# mcu_stm32f427.net
KiCad netlist of a schematic drawn in Altium Designer
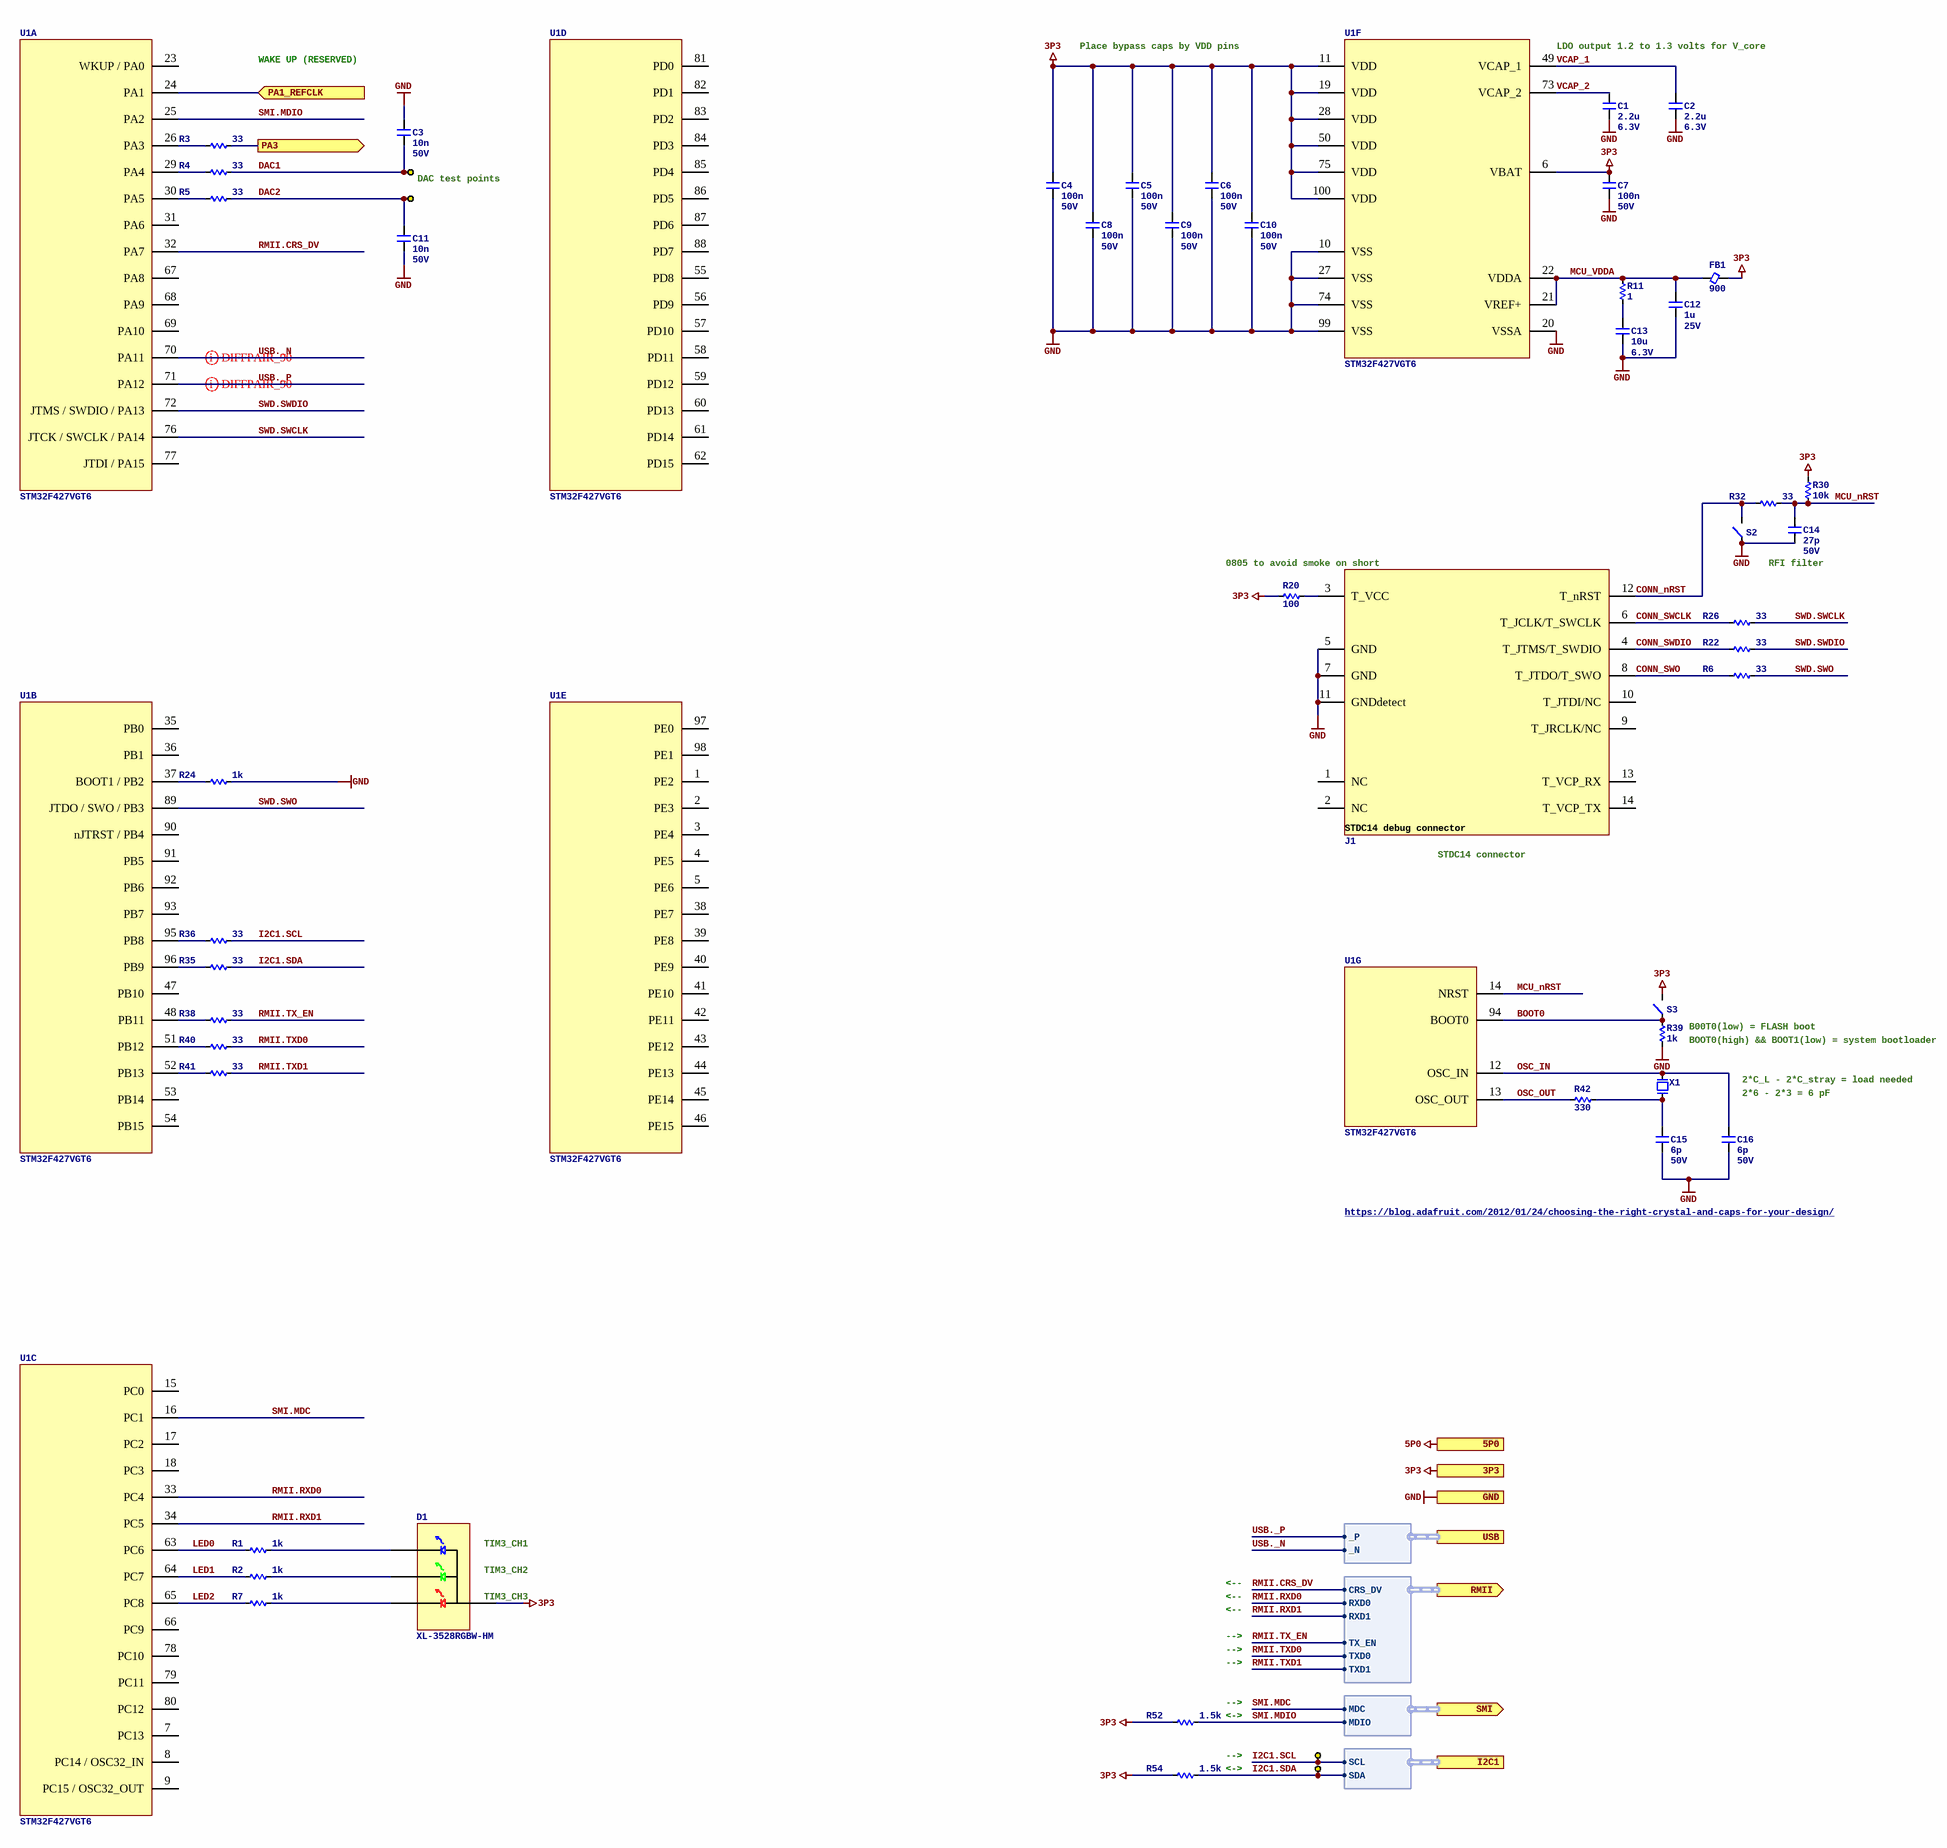
[diagram p0: mcu_stm32f427.SchDoc]

(export (version "E")
  (design (tool "Eeschema 10.0.6"))
  (components
    (comp (ref "C1")
      (value "GCM188R70J225KE22D")
      (footprint "C0603")
      (fields
        (field (name "CAPACITANCE") "2.2u")
        (field (name "MANUFACTURER") "Murata Electronics")
        (field (name "VOLTAGE RATING") "6.3V")
      )
      (libsource (lib "database") (part "__template_cap"))
    )
    (comp (ref "C2")
      (value "GCM188R70J225KE22D")
      (footprint "C0603")
      (fields
        (field (name "CAPACITANCE") "2.2u")
        (field (name "MANUFACTURER") "Murata Electronics")
        (field (name "VOLTAGE RATING") "6.3V")
      )
      (libsource (lib "database") (part "__template_cap"))
    )
    (comp (ref "C3")
      (value "CL05B103KB5NNNC")
      (footprint "C0402")
      (fields
        (field (name "CAPACITANCE") "10n")
        (field (name "MANUFACTURER") "Samsung Electro-Mechanics")
        (field (name "VOLTAGE RATING") "50V")
      )
      (libsource (lib "database") (part "__template_cap"))
    )
    (comp (ref "C4")
      (value "CL05B104KB54PNC")
      (footprint "C0402")
      (fields
        (field (name "CAPACITANCE") "100n")
        (field (name "MANUFACTURER") "Samsung Electro-Mechanics")
        (field (name "VOLTAGE RATING") "50V")
      )
      (libsource (lib "database") (part "__template_cap"))
    )
    (comp (ref "C5")
      (value "CL05B104KB54PNC")
      (footprint "C0402")
      (fields
        (field (name "CAPACITANCE") "100n")
        (field (name "MANUFACTURER") "Samsung Electro-Mechanics")
        (field (name "VOLTAGE RATING") "50V")
      )
      (libsource (lib "database") (part "__template_cap"))
    )
    (comp (ref "C6")
      (value "CL05B104KB54PNC")
      (footprint "C0402")
      (fields
        (field (name "CAPACITANCE") "100n")
        (field (name "MANUFACTURER") "Samsung Electro-Mechanics")
        (field (name "VOLTAGE RATING") "50V")
      )
      (libsource (lib "database") (part "__template_cap"))
    )
    (comp (ref "C7")
      (value "CL05B104KB54PNC")
      (footprint "C0402")
      (fields
        (field (name "CAPACITANCE") "100n")
        (field (name "MANUFACTURER") "Samsung Electro-Mechanics")
        (field (name "VOLTAGE RATING") "50V")
      )
      (libsource (lib "database") (part "__template_cap"))
    )
    (comp (ref "C8")
      (value "CL05B104KB54PNC")
      (footprint "C0402")
      (fields
        (field (name "CAPACITANCE") "100n")
        (field (name "MANUFACTURER") "Samsung Electro-Mechanics")
        (field (name "VOLTAGE RATING") "50V")
      )
      (libsource (lib "database") (part "__template_cap"))
    )
    (comp (ref "C9")
      (value "CL05B104KB54PNC")
      (footprint "C0402")
      (fields
        (field (name "CAPACITANCE") "100n")
        (field (name "MANUFACTURER") "Samsung Electro-Mechanics")
        (field (name "VOLTAGE RATING") "50V")
      )
      (libsource (lib "database") (part "__template_cap"))
    )
    (comp (ref "C10")
      (value "CL05B104KB54PNC")
      (footprint "C0402")
      (fields
        (field (name "CAPACITANCE") "100n")
        (field (name "MANUFACTURER") "Samsung Electro-Mechanics")
        (field (name "VOLTAGE RATING") "50V")
      )
      (libsource (lib "database") (part "__template_cap"))
    )
    (comp (ref "C11")
      (value "CL05B103KB5NNNC")
      (footprint "C0402")
      (fields
        (field (name "CAPACITANCE") "10n")
        (field (name "MANUFACTURER") "Samsung Electro-Mechanics")
        (field (name "VOLTAGE RATING") "50V")
      )
      (libsource (lib "database") (part "__template_cap"))
    )
    (comp (ref "C12")
      (value "CL10B105KA8NNNC")
      (footprint "C0603")
      (fields
        (field (name "CAPACITANCE") "1u")
        (field (name "MANUFACTURER") "Samsung Electro-Mechanics")
        (field (name "VOLTAGE RATING") "25V")
      )
      (libsource (lib "database") (part "__template_cap"))
    )
    (comp (ref "C13")
      (value "CC0805KKX7R5BB106")
      (footprint "C0805")
      (fields
        (field (name "CAPACITANCE") "10u")
        (field (name "MANUFACTURER") "YAGEO")
        (field (name "VOLTAGE RATING") "6.3V")
      )
      (libsource (lib "database") (part "__template_cap"))
    )
    (comp (ref "C14")
      (value "CC0402JRNPO9BN270")
      (footprint "C0402")
      (fields
        (field (name "CAPACITANCE") "27p")
        (field (name "MANUFACTURER") "YAGEO")
        (field (name "VOLTAGE RATING") "50V")
      )
      (libsource (lib "database") (part "__template_cap"))
    )
    (comp (ref "C15")
      (value "CC0402CRNPO9BN6R0")
      (footprint "C0402")
      (fields
        (field (name "CAPACITANCE") "6p")
        (field (name "MANUFACTURER") "YAGEO")
        (field (name "VOLTAGE RATING") "50V")
      )
      (libsource (lib "database") (part "__template_cap"))
    )
    (comp (ref "C16")
      (value "CC0402CRNPO9BN6R0")
      (footprint "C0402")
      (fields
        (field (name "CAPACITANCE") "6p")
        (field (name "MANUFACTURER") "YAGEO")
        (field (name "VOLTAGE RATING") "50V")
      )
      (libsource (lib "database") (part "__template_cap"))
    )
    (comp (ref "D1")
      (value "XL-3528RGBW-HM")
      (footprint "LED_RGB_SMD3528-4P")
      (description "LED Multi-Color Chip Red/Green/Blue 621nm/525nm/468nm 25mA/15mA/15mA 4-Pin PLCC T/R")
      (fields (field (name "MANUFACTURER") "XINGLIGHT"))
      (libsource (lib "SSCP") (part "LED_RGB_XL-3528RGBW-HM"))
    )
    (comp (ref "FB1")
      (value "BLM15PX601SN1D")
      (footprint "FB0402")
      (fields (field (name "MANUFACTURER") "Murata Electronics") (field (name "CURRENT RATING (MA)") "900"))
      (libsource (lib "database") (part "__template_fb"))
    )
    (comp (ref "J1")
      (value "FTSH-107-01-L-DV-K-A")
      (footprint "SAMTEC_FTSH-107-01-L-DV-K-A")
      (description "Connector Header Surface Mount 14 position 0.050\" (1.27mm)")
      (fields (field (name "MANUFACTURER") "Samtec"))
      (libsource (lib "SSCP") (part "CONN_14POS_50MIL_ST_CORTEX_DEBUG_VCP"))
    )
    (comp (ref "R1")
      (value "1k")
      (footprint "R0402")
      (fields
        (field (name "TOLERANCE") "1%")
        (field (name "MANUFACTURER PART NUMBER") "0402WGF1001TCE")
        (field (name "MANUFACTURER") "UNI-ROYAL(Uniroyal Elec)")
      )
      (libsource (lib "database") (part "__template_resistor"))
    )
    (comp (ref "R2")
      (value "1k")
      (footprint "R0402")
      (fields
        (field (name "TOLERANCE") "1%")
        (field (name "MANUFACTURER PART NUMBER") "0402WGF1001TCE")
        (field (name "MANUFACTURER") "UNI-ROYAL(Uniroyal Elec)")
      )
      (libsource (lib "database") (part "__template_resistor"))
    )
    (comp (ref "R3")
      (value "33")
      (footprint "R0402")
      (fields
        (field (name "TOLERANCE") "1%")
        (field (name "MANUFACTURER PART NUMBER") "CRCW040233R0FKED")
        (field (name "MANUFACTURER") "Vishay Intertech")
      )
      (libsource (lib "database") (part "__template_resistor"))
    )
    (comp (ref "R4")
      (value "33")
      (footprint "R0402")
      (fields
        (field (name "TOLERANCE") "1%")
        (field (name "MANUFACTURER PART NUMBER") "CRCW040233R0FKED")
        (field (name "MANUFACTURER") "Vishay Intertech")
      )
      (libsource (lib "database") (part "__template_resistor"))
    )
    (comp (ref "R5")
      (value "33")
      (footprint "R0402")
      (fields
        (field (name "TOLERANCE") "1%")
        (field (name "MANUFACTURER PART NUMBER") "CRCW040233R0FKED")
        (field (name "MANUFACTURER") "Vishay Intertech")
      )
      (libsource (lib "database") (part "__template_resistor"))
    )
    (comp (ref "R6")
      (value "33")
      (footprint "R0402")
      (fields
        (field (name "TOLERANCE") "1%")
        (field (name "MANUFACTURER PART NUMBER") "CRCW040233R0FKED")
        (field (name "MANUFACTURER") "Vishay Intertech")
      )
      (libsource (lib "database") (part "__template_resistor"))
    )
    (comp (ref "R7")
      (value "1k")
      (footprint "R0402")
      (fields
        (field (name "TOLERANCE") "1%")
        (field (name "MANUFACTURER PART NUMBER") "0402WGF1001TCE")
        (field (name "MANUFACTURER") "UNI-ROYAL(Uniroyal Elec)")
      )
      (libsource (lib "database") (part "__template_resistor"))
    )
    (comp (ref "R11")
      (value "1")
      (footprint "R0402")
      (fields
        (field (name "TOLERANCE") "1%")
        (field (name "MANUFACTURER PART NUMBER") "CRCW04021R00FKEDC")
        (field (name "MANUFACTURER") "Vishay Intertech")
      )
      (libsource (lib "database") (part "__template_resistor"))
    )
    (comp (ref "R20")
      (value "100")
      (footprint "R0805")
      (fields
        (field (name "TOLERANCE") "1%")
        (field (name "MANUFACTURER PART NUMBER") "AR05FTC1000")
        (field (name "MANUFACTURER") "Viking Tech")
      )
      (libsource (lib "database") (part "__template_resistor"))
    )
    (comp (ref "R22")
      (value "33")
      (footprint "R0402")
      (fields
        (field (name "TOLERANCE") "1%")
        (field (name "MANUFACTURER PART NUMBER") "CRCW040233R0FKED")
        (field (name "MANUFACTURER") "Vishay Intertech")
      )
      (libsource (lib "database") (part "__template_resistor"))
    )
    (comp (ref "R24")
      (value "1k")
      (footprint "R0402")
      (fields
        (field (name "TOLERANCE") "1%")
        (field (name "MANUFACTURER PART NUMBER") "0402WGF1001TCE")
        (field (name "MANUFACTURER") "UNI-ROYAL(Uniroyal Elec)")
      )
      (libsource (lib "database") (part "__template_resistor"))
    )
    (comp (ref "R26")
      (value "33")
      (footprint "R0402")
      (fields
        (field (name "TOLERANCE") "1%")
        (field (name "MANUFACTURER PART NUMBER") "CRCW040233R0FKED")
        (field (name "MANUFACTURER") "Vishay Intertech")
      )
      (libsource (lib "database") (part "__template_resistor"))
    )
    (comp (ref "R30")
      (value "10k")
      (footprint "R0402")
      (fields
        (field (name "TOLERANCE") "1%")
        (field (name "MANUFACTURER PART NUMBER") "0402WGF1002TCE")
        (field (name "MANUFACTURER") "UNI-ROYAL(Uniroyal Elec)")
      )
      (libsource (lib "database") (part "__template_resistor"))
    )
    (comp (ref "R32")
      (value "33")
      (footprint "R0402")
      (fields
        (field (name "TOLERANCE") "1%")
        (field (name "MANUFACTURER PART NUMBER") "CRCW040233R0FKED")
        (field (name "MANUFACTURER") "Vishay Intertech")
      )
      (libsource (lib "database") (part "__template_resistor"))
    )
    (comp (ref "R35")
      (value "33")
      (footprint "R0402")
      (fields
        (field (name "TOLERANCE") "1%")
        (field (name "MANUFACTURER PART NUMBER") "CRCW040233R0FKED")
        (field (name "MANUFACTURER") "Vishay Intertech")
      )
      (libsource (lib "database") (part "__template_resistor"))
    )
    (comp (ref "R36")
      (value "33")
      (footprint "R0402")
      (fields
        (field (name "TOLERANCE") "1%")
        (field (name "MANUFACTURER PART NUMBER") "CRCW040233R0FKED")
        (field (name "MANUFACTURER") "Vishay Intertech")
      )
      (libsource (lib "database") (part "__template_resistor"))
    )
    (comp (ref "R38")
      (value "33")
      (footprint "R0402")
      (fields
        (field (name "TOLERANCE") "1%")
        (field (name "MANUFACTURER PART NUMBER") "CRCW040233R0FKED")
        (field (name "MANUFACTURER") "Vishay Intertech")
      )
      (libsource (lib "database") (part "__template_resistor"))
    )
    (comp (ref "R39")
      (value "1k")
      (footprint "R0402")
      (fields
        (field (name "TOLERANCE") "1%")
        (field (name "MANUFACTURER PART NUMBER") "0402WGF1001TCE")
        (field (name "MANUFACTURER") "UNI-ROYAL(Uniroyal Elec)")
      )
      (libsource (lib "database") (part "__template_resistor"))
    )
    (comp (ref "R40")
      (value "33")
      (footprint "R0402")
      (fields
        (field (name "TOLERANCE") "1%")
        (field (name "MANUFACTURER PART NUMBER") "CRCW040233R0FKED")
        (field (name "MANUFACTURER") "Vishay Intertech")
      )
      (libsource (lib "database") (part "__template_resistor"))
    )
    (comp (ref "R41")
      (value "33")
      (footprint "R0402")
      (fields
        (field (name "TOLERANCE") "1%")
        (field (name "MANUFACTURER PART NUMBER") "CRCW040233R0FKED")
        (field (name "MANUFACTURER") "Vishay Intertech")
      )
      (libsource (lib "database") (part "__template_resistor"))
    )
    (comp (ref "R42")
      (value "330")
      (footprint "R0402")
      (fields
        (field (name "TOLERANCE") "1%")
        (field (name "MANUFACTURER PART NUMBER") "0402WGF3300TCE")
        (field (name "MANUFACTURER") "UNI-ROYAL(Uniroyal Elec)")
      )
      (libsource (lib "database") (part "__template_resistor"))
    )
    (comp (ref "R52")
      (value "1.5k")
      (footprint "R0402")
      (fields
        (field (name "TOLERANCE") "1%")
        (field (name "MANUFACTURER PART NUMBER") "0402WGF1501TCE")
        (field (name "MANUFACTURER") "UNI-ROYAL(Uniroyal Elec)")
      )
      (libsource (lib "database") (part "__template_resistor"))
    )
    (comp (ref "R54")
      (value "1.5k")
      (footprint "R0402")
      (fields
        (field (name "TOLERANCE") "1%")
        (field (name "MANUFACTURER PART NUMBER") "0402WGF1501TCE")
        (field (name "MANUFACTURER") "UNI-ROYAL(Uniroyal Elec)")
      )
      (libsource (lib "database") (part "__template_resistor"))
    )
    (comp (ref "S2")
      (value "TS-1092S-B3D2-G")
      (footprint "SWITCH_TS-1092S-B3D2-G")
      (description "SWITCH TACTILE SPST-NO")
      (fields (field (name "MANUFACTURER") "Yuandi"))
      (libsource (lib "SSCP") (part "SWITCH_TS-1092S-B3D2-G"))
    )
    (comp (ref "S3")
      (value "TS-1092S-B3D2-G")
      (footprint "SWITCH_TS-1092S-B3D2-G")
      (description "SWITCH TACTILE SPST-NO")
      (fields (field (name "MANUFACTURER") "Yuandi"))
      (libsource (lib "SSCP") (part "SWITCH_TS-1092S-B3D2-G"))
    )
    (comp (ref "TP1")
      (value "~")
      (footprint "TP_RH-5002")
      (description "THT white clip turret")
      (fields (field (name "MANUFACTURER PART NUMBER") "RH-5002") (field (name "MANUFACTURER") "ronghe"))
      (libsource (lib "database") (part "__template_testpoint"))
    )
    (comp (ref "TP2")
      (value "~")
      (footprint "TP_RH-5002")
      (description "THT white clip turret")
      (fields (field (name "MANUFACTURER PART NUMBER") "RH-5002") (field (name "MANUFACTURER") "ronghe"))
      (libsource (lib "database") (part "__template_testpoint"))
    )
    (comp (ref "TP62")
      (value "~")
      (footprint "TP_GRABBY")
      (description "EMBEDDED TEST POINT FOR SALEAE TEST CLIPS")
      (libsource (lib "SSCP") (part "TEST_GRABBER"))
    )
    (comp (ref "TP63")
      (value "~")
      (footprint "TP_GRABBY")
      (description "EMBEDDED TEST POINT FOR SALEAE TEST CLIPS")
      (libsource (lib "SSCP") (part "TEST_GRABBER"))
    )
    (comp (ref "U1")
      (value "STM32F427VGT6")
      (footprint "100TQFP14")
      (description "ARM Cortex®-M4 STM32F4 Microcontroller IC 32-Bit 180MHz 1MB (1M x 8) FLASH 100-LQFP (14x14)")
      (fields
        (field (name "MANUFACTURER PART NUMBER") "STM32F427VGT6")
        (field (name "MANUFACTURER") "ST Microelectronics")
      )
      (libsource (lib "SSCP") (part "MCU_STM32F427VGT6"))
    )
    (comp (ref "X1")
      (value "XTAL_XRCGB25M000F3A00R0")
      (footprint "4_SMD_2.0X1.6MM")
      (description "CRYSTAL 25.000MHZ 6PF SMD")
      (fields
        (field (name "MANUFACTURER") "Murata")
        (field (name "MANUFACTURER PART NUMBER") "XRCGB25M000F3A00R0")
      )
      (libsource (lib "SSCP") (part "XTAL_XRCGB25M000F3A00R0"))
    )
  )
  (nets
    (net (code "5") (name "/BOOT0") (class "Default")
      (node (ref "R39") (pin "1") (pintype "passive"))
      (node (ref "S3") (pin "1") (pintype "passive"))
      (node (ref "U1") (pin "94") (pinfunction "BOOT0_94") (pintype "passive"))
    )
    (net (code "6") (name "/CONN_SWCLK") (class "Default")
      (node (ref "J1") (pin "6") (pinfunction "T_JCLK/T_SWCLK_6") (pintype "passive"))
      (node (ref "R26") (pin "2") (pintype "passive"))
    )
    (net (code "7") (name "/CONN_SWDIO") (class "Default")
      (node (ref "J1") (pin "4") (pinfunction "T_JTMS/T_SWDIO_4") (pintype "passive"))
      (node (ref "R22") (pin "2") (pintype "passive"))
    )
    (net (code "8") (name "/CONN_SWO") (class "Default")
      (node (ref "J1") (pin "8") (pinfunction "T_JTDO/T_SWO_8") (pintype "passive"))
      (node (ref "R6") (pin "2") (pintype "passive"))
    )
    (net (code "9") (name "/CONN_nRST") (class "Default")
      (node (ref "J1") (pin "12") (pinfunction "T_nRST_12") (pintype "passive"))
      (node (ref "R32") (pin "2") (pintype "passive"))
      (node (ref "S2") (pin "2") (pintype "passive"))
    )
    (net (code "10") (name "/DAC1") (class "Default")
      (node (ref "C3") (pin "1") (pintype "passive"))
      (node (ref "R4") (pin "1") (pintype "passive"))
      (node (ref "TP1") (pin "1") (pintype "passive"))
    )
    (net (code "11") (name "/DAC2") (class "Default")
      (node (ref "C11") (pin "1") (pintype "passive"))
      (node (ref "R5") (pin "1") (pintype "passive"))
      (node (ref "TP2") (pin "1") (pintype "passive"))
    )
    (net (code "12") (name "/I2C1.SCL") (class "Default")
      (node (ref "R36") (pin "1") (pintype "passive"))
      (node (ref "TP62") (pin "1") (pintype "passive"))
    )
    (net (code "13") (name "/I2C1.SDA") (class "Default")
      (node (ref "R35") (pin "1") (pintype "passive"))
      (node (ref "R54") (pin "1") (pintype "passive"))
      (node (ref "TP63") (pin "1") (pintype "passive"))
    )
    (net (code "14") (name "/LED0") (class "Default")
      (node (ref "R1") (pin "2") (pintype "passive"))
      (node (ref "U1") (pin "63") (pinfunction "PC6_63") (pintype "passive"))
    )
    (net (code "15") (name "/LED1") (class "Default")
      (node (ref "R2") (pin "2") (pintype "passive"))
      (node (ref "U1") (pin "64") (pinfunction "PC7_64") (pintype "passive"))
    )
    (net (code "16") (name "/LED2") (class "Default")
      (node (ref "R7") (pin "2") (pintype "passive"))
      (node (ref "U1") (pin "65") (pinfunction "PC8_65") (pintype "passive"))
    )
    (net (code "17") (name "/MCU_VDDA") (class "Default")
      (node (ref "C12") (pin "1") (pintype "passive"))
      (node (ref "FB1") (pin "1") (pintype "passive"))
      (node (ref "R11") (pin "2") (pintype "passive"))
      (node (ref "U1") (pin "21") (pinfunction "VREF+_21") (pintype "passive"))
      (node (ref "U1") (pin "22") (pinfunction "VDDA_22") (pintype "passive"))
    )
    (net (code "18") (name "/MCU_nRST") (class "Default")
      (node (ref "C14") (pin "1") (pintype "passive"))
      (node (ref "R30") (pin "2") (pintype "passive"))
      (node (ref "R32") (pin "1") (pintype "passive"))
      (node (ref "U1") (pin "14") (pinfunction "NRST_14") (pintype "passive"))
    )
    (net (code "19") (name "/OSC_IN") (class "Default")
      (node (ref "C16") (pin "1") (pintype "passive"))
      (node (ref "U1") (pin "12") (pinfunction "OSC_IN_12") (pintype "passive"))
      (node (ref "X1") (pin "3") (pinfunction "3_3") (pintype "passive"))
    )
    (net (code "20") (name "/OSC_OUT") (class "Default")
      (node (ref "R42") (pin "1") (pintype "passive"))
      (node (ref "U1") (pin "13") (pinfunction "OSC_OUT_13") (pintype "passive"))
    )
    (net (code "21") (name "/PA1_REFCLK") (class "Default")
      (node (ref "U1") (pin "24") (pinfunction "PA1_24") (pintype "passive"))
    )
    (net (code "22") (name "/PA3") (class "Default") (node (ref "R3") (pin "1") (pintype "passive")))
    (net (code "23") (name "/RMII.CRS_DV") (class "Default")
      (node (ref "U1") (pin "32") (pinfunction "PA7_32") (pintype "passive"))
    )
    (net (code "24") (name "/RMII.RXD0") (class "Default")
      (node (ref "U1") (pin "33") (pinfunction "PC4_33") (pintype "passive"))
    )
    (net (code "25") (name "/RMII.RXD1") (class "Default")
      (node (ref "U1") (pin "34") (pinfunction "PC5_34") (pintype "passive"))
    )
    (net (code "26") (name "/RMII.TXD0") (class "Default") (node (ref "R40") (pin "1") (pintype "passive")))
    (net (code "27") (name "/RMII.TXD1") (class "Default") (node (ref "R41") (pin "1") (pintype "passive")))
    (net (code "28") (name "/RMII.TX_EN") (class "Default") (node (ref "R38") (pin "1") (pintype "passive")))
    (net (code "29") (name "/SMI.MDC") (class "Default")
      (node (ref "U1") (pin "16") (pinfunction "PC1_16") (pintype "passive"))
    )
    (net (code "30") (name "/SMI.MDIO") (class "Default")
      (node (ref "R52") (pin "1") (pintype "passive"))
      (node (ref "U1") (pin "25") (pinfunction "PA2_25") (pintype "passive"))
    )
    (net (code "31") (name "/SWD.SWCLK") (class "Default")
      (node (ref "R26") (pin "1") (pintype "passive"))
      (node (ref "U1") (pin "76") (pinfunction "JTCK_/_SWCLK_/_PA14_76") (pintype "passive"))
    )
    (net (code "32") (name "/SWD.SWDIO") (class "Default")
      (node (ref "R22") (pin "1") (pintype "passive"))
      (node (ref "U1") (pin "72") (pinfunction "JTMS_/_SWDIO_/_PA13_72") (pintype "passive"))
    )
    (net (code "33") (name "/SWD.SWO") (class "Default")
      (node (ref "R6") (pin "1") (pintype "passive"))
      (node (ref "U1") (pin "89") (pinfunction "JTDO_/_SWO_/_PB3_89") (pintype "passive"))
    )
    (net (code "34") (name "/USB._N") (class "Default")
      (node (ref "U1") (pin "70") (pinfunction "PA11_70") (pintype "passive"))
    )
    (net (code "35") (name "/USB._P") (class "Default")
      (node (ref "U1") (pin "71") (pinfunction "PA12_71") (pintype "passive"))
    )
    (net (code "36") (name "/VCAP_1") (class "Default")
      (node (ref "C2") (pin "1") (pintype "passive"))
      (node (ref "U1") (pin "49") (pinfunction "VCAP_1_49") (pintype "passive"))
    )
    (net (code "37") (name "/VCAP_2") (class "Default")
      (node (ref "C1") (pin "1") (pintype "passive"))
      (node (ref "U1") (pin "73") (pinfunction "VCAP_2_73") (pintype "passive"))
    )
    (net (code "42") (name "3P3") (class "Default")
      (node (ref "C10") (pin "1") (pintype "passive"))
      (node (ref "C4") (pin "1") (pintype "passive"))
      (node (ref "C5") (pin "1") (pintype "passive"))
      (node (ref "C6") (pin "1") (pintype "passive"))
      (node (ref "C7") (pin "1") (pintype "passive"))
      (node (ref "C8") (pin "1") (pintype "passive"))
      (node (ref "C9") (pin "1") (pintype "passive"))
      (node (ref "D1") (pin "2") (pintype "passive"))
      (node (ref "FB1") (pin "2") (pintype "passive"))
      (node (ref "R20") (pin "2") (pintype "passive"))
      (node (ref "R30") (pin "1") (pintype "passive"))
      (node (ref "R52") (pin "2") (pintype "passive"))
      (node (ref "R54") (pin "2") (pintype "passive"))
      (node (ref "S3") (pin "2") (pintype "passive"))
      (node (ref "U1") (pin "100") (pinfunction "VDD_100") (pintype "passive"))
      (node (ref "U1") (pin "11") (pinfunction "VDD_11") (pintype "passive"))
      (node (ref "U1") (pin "19") (pinfunction "VDD_19") (pintype "passive"))
      (node (ref "U1") (pin "28") (pinfunction "VDD_28") (pintype "passive"))
      (node (ref "U1") (pin "50") (pinfunction "VDD_50") (pintype "passive"))
      (node (ref "U1") (pin "6") (pinfunction "VBAT_6") (pintype "passive"))
      (node (ref "U1") (pin "75") (pinfunction "VDD_75") (pintype "passive"))
    )
    (net (code "44") (name "GND") (class "Default")
      (node (ref "C1") (pin "2") (pintype "passive"))
      (node (ref "C10") (pin "2") (pintype "passive"))
      (node (ref "C11") (pin "2") (pintype "passive"))
      (node (ref "C12") (pin "2") (pintype "passive"))
      (node (ref "C13") (pin "2") (pintype "passive"))
      (node (ref "C14") (pin "2") (pintype "passive"))
      (node (ref "C15") (pin "2") (pintype "passive"))
      (node (ref "C16") (pin "2") (pintype "passive"))
      (node (ref "C2") (pin "2") (pintype "passive"))
      (node (ref "C3") (pin "2") (pintype "passive"))
      (node (ref "C4") (pin "2") (pintype "passive"))
      (node (ref "C5") (pin "2") (pintype "passive"))
      (node (ref "C6") (pin "2") (pintype "passive"))
      (node (ref "C7") (pin "2") (pintype "passive"))
      (node (ref "C8") (pin "2") (pintype "passive"))
      (node (ref "C9") (pin "2") (pintype "passive"))
      (node (ref "J1") (pin "11") (pinfunction "GNDdetect_11") (pintype "passive"))
      (node (ref "J1") (pin "5") (pinfunction "GND_5") (pintype "passive"))
      (node (ref "J1") (pin "7") (pinfunction "GND_7") (pintype "passive"))
      (node (ref "R24") (pin "1") (pintype "passive"))
      (node (ref "R39") (pin "2") (pintype "passive"))
      (node (ref "S2") (pin "1") (pintype "passive"))
      (node (ref "U1") (pin "10") (pinfunction "VSS_10") (pintype "passive"))
      (node (ref "U1") (pin "20") (pinfunction "VSSA_20") (pintype "passive"))
      (node (ref "U1") (pin "27") (pinfunction "VSS_27") (pintype "passive"))
      (node (ref "U1") (pin "74") (pinfunction "VSS_74") (pintype "passive"))
      (node (ref "U1") (pin "99") (pinfunction "VSS_99") (pintype "passive"))
    )
    (net (code "45") (name "Net-(C13-Pad1)") (class "Default")
      (node (ref "C13") (pin "1") (pintype "passive"))
      (node (ref "R11") (pin "1") (pintype "passive"))
    )
    (net (code "46") (name "Net-(C15-Pad1)") (class "Default")
      (node (ref "C15") (pin "1") (pintype "passive"))
      (node (ref "R42") (pin "2") (pintype "passive"))
      (node (ref "X1") (pin "1") (pinfunction "1_1") (pintype "passive"))
    )
    (net (code "47") (name "Net-(D1-Pad1)") (class "Default")
      (node (ref "D1") (pin "1") (pintype "passive"))
      (node (ref "R7") (pin "1") (pintype "passive"))
    )
    (net (code "48") (name "Net-(D1-Pad3)") (class "Default")
      (node (ref "D1") (pin "3") (pintype "passive"))
      (node (ref "R2") (pin "1") (pintype "passive"))
    )
    (net (code "49") (name "Net-(D1-Pad4)") (class "Default")
      (node (ref "D1") (pin "4") (pintype "passive"))
      (node (ref "R1") (pin "1") (pintype "passive"))
    )
    (net (code "50") (name "Net-(J1-T_VCC)") (class "Default")
      (node (ref "J1") (pin "3") (pinfunction "T_VCC_3") (pintype "passive"))
      (node (ref "R20") (pin "1") (pintype "passive"))
    )
    (net (code "51") (name "Net-(U1A-PA3)") (class "Default")
      (node (ref "R3") (pin "2") (pintype "passive"))
      (node (ref "U1") (pin "26") (pinfunction "PA3_26") (pintype "passive"))
    )
    (net (code "52") (name "Net-(U1A-PA4)") (class "Default")
      (node (ref "R4") (pin "2") (pintype "passive"))
      (node (ref "U1") (pin "29") (pinfunction "PA4_29") (pintype "passive"))
    )
    (net (code "53") (name "Net-(U1A-PA5)") (class "Default")
      (node (ref "R5") (pin "2") (pintype "passive"))
      (node (ref "U1") (pin "30") (pinfunction "PA5_30") (pintype "passive"))
    )
    (net (code "54") (name "Net-(U1B-BOOT1_{slash}_PB2)") (class "Default")
      (node (ref "R24") (pin "2") (pintype "passive"))
      (node (ref "U1") (pin "37") (pinfunction "BOOT1_/_PB2_37") (pintype "passive"))
    )
    (net (code "55") (name "Net-(U1B-PB8)") (class "Default")
      (node (ref "R36") (pin "2") (pintype "passive"))
      (node (ref "U1") (pin "95") (pinfunction "PB8_95") (pintype "passive"))
    )
    (net (code "56") (name "Net-(U1B-PB9)") (class "Default")
      (node (ref "R35") (pin "2") (pintype "passive"))
      (node (ref "U1") (pin "96") (pinfunction "PB9_96") (pintype "passive"))
    )
    (net (code "57") (name "Net-(U1B-PB11)") (class "Default")
      (node (ref "R38") (pin "2") (pintype "passive"))
      (node (ref "U1") (pin "48") (pinfunction "PB11_48") (pintype "passive"))
    )
    (net (code "58") (name "Net-(U1B-PB12)") (class "Default")
      (node (ref "R40") (pin "2") (pintype "passive"))
      (node (ref "U1") (pin "51") (pinfunction "PB12_51") (pintype "passive"))
    )
    (net (code "59") (name "Net-(U1B-PB13)") (class "Default")
      (node (ref "R41") (pin "2") (pintype "passive"))
      (node (ref "U1") (pin "52") (pinfunction "PB13_52") (pintype "passive"))
    )
    (net (code "60") (name "unconnected-(J1-NC-Pad1)") (class "Default")
      (node (ref "J1") (pin "1") (pinfunction "NC_1") (pintype "passive"))
    )
    (net (code "61") (name "unconnected-(J1-NC-Pad2)") (class "Default")
      (node (ref "J1") (pin "2") (pinfunction "NC_2") (pintype "passive"))
    )
    (net (code "62") (name "unconnected-(J1-T_JRCLK{slash}NC-Pad9)") (class "Default")
      (node (ref "J1") (pin "9") (pinfunction "T_JRCLK/NC_9") (pintype "passive"))
    )
    (net (code "63") (name "unconnected-(J1-T_JTDI{slash}NC-Pad10)") (class "Default")
      (node (ref "J1") (pin "10") (pinfunction "T_JTDI/NC_10") (pintype "passive"))
    )
    (net (code "64") (name "unconnected-(J1-T_VCP_RX-Pad13)") (class "Default")
      (node (ref "J1") (pin "13") (pinfunction "T_VCP_RX_13") (pintype "passive"))
    )
    (net (code "65") (name "unconnected-(J1-T_VCP_TX-Pad14)") (class "Default")
      (node (ref "J1") (pin "14") (pinfunction "T_VCP_TX_14") (pintype "passive"))
    )
    (net (code "66") (name "unconnected-(U1A-JTDI_{slash}_PA15-Pad77)") (class "Default")
      (node (ref "U1") (pin "77") (pinfunction "JTDI_/_PA15_77") (pintype "passive"))
    )
    (net (code "67") (name "unconnected-(U1A-PA6-Pad31)") (class "Default")
      (node (ref "U1") (pin "31") (pinfunction "PA6_31") (pintype "passive"))
    )
    (net (code "68") (name "unconnected-(U1A-PA8-Pad67)") (class "Default")
      (node (ref "U1") (pin "67") (pinfunction "PA8_67") (pintype "passive"))
    )
    (net (code "69") (name "unconnected-(U1A-PA9-Pad68)") (class "Default")
      (node (ref "U1") (pin "68") (pinfunction "PA9_68") (pintype "passive"))
    )
    (net (code "70") (name "unconnected-(U1A-PA10-Pad69)") (class "Default")
      (node (ref "U1") (pin "69") (pinfunction "PA10_69") (pintype "passive"))
    )
    (net (code "71") (name "unconnected-(U1A-WKUP_{slash}_PA0-Pad23)") (class "Default")
      (node (ref "U1") (pin "23") (pinfunction "WKUP_/_PA0_23") (pintype "passive"))
    )
    (net (code "72") (name "unconnected-(U1B-PB0-Pad35)") (class "Default")
      (node (ref "U1") (pin "35") (pinfunction "PB0_35") (pintype "passive"))
    )
    (net (code "73") (name "unconnected-(U1B-PB1-Pad36)") (class "Default")
      (node (ref "U1") (pin "36") (pinfunction "PB1_36") (pintype "passive"))
    )
    (net (code "74") (name "unconnected-(U1B-PB5-Pad91)") (class "Default")
      (node (ref "U1") (pin "91") (pinfunction "PB5_91") (pintype "passive"))
    )
    (net (code "75") (name "unconnected-(U1B-PB6-Pad92)") (class "Default")
      (node (ref "U1") (pin "92") (pinfunction "PB6_92") (pintype "passive"))
    )
    (net (code "76") (name "unconnected-(U1B-PB7-Pad93)") (class "Default")
      (node (ref "U1") (pin "93") (pinfunction "PB7_93") (pintype "passive"))
    )
    (net (code "77") (name "unconnected-(U1B-PB10-Pad47)") (class "Default")
      (node (ref "U1") (pin "47") (pinfunction "PB10_47") (pintype "passive"))
    )
    (net (code "78") (name "unconnected-(U1B-PB14-Pad53)") (class "Default")
      (node (ref "U1") (pin "53") (pinfunction "PB14_53") (pintype "passive"))
    )
    (net (code "79") (name "unconnected-(U1B-PB15-Pad54)") (class "Default")
      (node (ref "U1") (pin "54") (pinfunction "PB15_54") (pintype "passive"))
    )
    (net (code "80") (name "unconnected-(U1B-nJTRST_{slash}_PB4-Pad90)") (class "Default")
      (node (ref "U1") (pin "90") (pinfunction "nJTRST_/_PB4_90") (pintype "passive"))
    )
    (net (code "81") (name "unconnected-(U1C-PC0-Pad15)") (class "Default")
      (node (ref "U1") (pin "15") (pinfunction "PC0_15") (pintype "passive"))
    )
    (net (code "82") (name "unconnected-(U1C-PC2-Pad17)") (class "Default")
      (node (ref "U1") (pin "17") (pinfunction "PC2_17") (pintype "passive"))
    )
    (net (code "83") (name "unconnected-(U1C-PC3-Pad18)") (class "Default")
      (node (ref "U1") (pin "18") (pinfunction "PC3_18") (pintype "passive"))
    )
    (net (code "84") (name "unconnected-(U1C-PC9-Pad66)") (class "Default")
      (node (ref "U1") (pin "66") (pinfunction "PC9_66") (pintype "passive"))
    )
    (net (code "85") (name "unconnected-(U1C-PC10-Pad78)") (class "Default")
      (node (ref "U1") (pin "78") (pinfunction "PC10_78") (pintype "passive"))
    )
    (net (code "86") (name "unconnected-(U1C-PC11-Pad79)") (class "Default")
      (node (ref "U1") (pin "79") (pinfunction "PC11_79") (pintype "passive"))
    )
    (net (code "87") (name "unconnected-(U1C-PC12-Pad80)") (class "Default")
      (node (ref "U1") (pin "80") (pinfunction "PC12_80") (pintype "passive"))
    )
    (net (code "88") (name "unconnected-(U1C-PC13-Pad7)") (class "Default")
      (node (ref "U1") (pin "7") (pinfunction "PC13_7") (pintype "passive"))
    )
    (net (code "89") (name "unconnected-(U1C-PC14_{slash}_OSC32_IN-Pad8)") (class "Default")
      (node (ref "U1") (pin "8") (pinfunction "PC14_/_OSC32_IN_8") (pintype "passive"))
    )
    (net (code "90") (name "unconnected-(U1C-PC15_{slash}_OSC32_OUT-Pad9)") (class "Default")
      (node (ref "U1") (pin "9") (pinfunction "PC15_/_OSC32_OUT_9") (pintype "passive"))
    )
    (net (code "91") (name "unconnected-(U1D-PD0-Pad81)") (class "Default")
      (node (ref "U1") (pin "81") (pinfunction "PD0_81") (pintype "passive"))
    )
    (net (code "92") (name "unconnected-(U1D-PD1-Pad82)") (class "Default")
      (node (ref "U1") (pin "82") (pinfunction "PD1_82") (pintype "passive"))
    )
    (net (code "93") (name "unconnected-(U1D-PD2-Pad83)") (class "Default")
      (node (ref "U1") (pin "83") (pinfunction "PD2_83") (pintype "passive"))
    )
    (net (code "94") (name "unconnected-(U1D-PD3-Pad84)") (class "Default")
      (node (ref "U1") (pin "84") (pinfunction "PD3_84") (pintype "passive"))
    )
    (net (code "95") (name "unconnected-(U1D-PD4-Pad85)") (class "Default")
      (node (ref "U1") (pin "85") (pinfunction "PD4_85") (pintype "passive"))
    )
    (net (code "96") (name "unconnected-(U1D-PD5-Pad86)") (class "Default")
      (node (ref "U1") (pin "86") (pinfunction "PD5_86") (pintype "passive"))
    )
    (net (code "97") (name "unconnected-(U1D-PD6-Pad87)") (class "Default")
      (node (ref "U1") (pin "87") (pinfunction "PD6_87") (pintype "passive"))
    )
    (net (code "98") (name "unconnected-(U1D-PD7-Pad88)") (class "Default")
      (node (ref "U1") (pin "88") (pinfunction "PD7_88") (pintype "passive"))
    )
    (net (code "99") (name "unconnected-(U1D-PD8-Pad55)") (class "Default")
      (node (ref "U1") (pin "55") (pinfunction "PD8_55") (pintype "passive"))
    )
    (net (code "100") (name "unconnected-(U1D-PD9-Pad56)") (class "Default")
      (node (ref "U1") (pin "56") (pinfunction "PD9_56") (pintype "passive"))
    )
    (net (code "101") (name "unconnected-(U1D-PD10-Pad57)") (class "Default")
      (node (ref "U1") (pin "57") (pinfunction "PD10_57") (pintype "passive"))
    )
    (net (code "102") (name "unconnected-(U1D-PD11-Pad58)") (class "Default")
      (node (ref "U1") (pin "58") (pinfunction "PD11_58") (pintype "passive"))
    )
    (net (code "103") (name "unconnected-(U1D-PD12-Pad59)") (class "Default")
      (node (ref "U1") (pin "59") (pinfunction "PD12_59") (pintype "passive"))
    )
    (net (code "104") (name "unconnected-(U1D-PD13-Pad60)") (class "Default")
      (node (ref "U1") (pin "60") (pinfunction "PD13_60") (pintype "passive"))
    )
    (net (code "105") (name "unconnected-(U1D-PD14-Pad61)") (class "Default")
      (node (ref "U1") (pin "61") (pinfunction "PD14_61") (pintype "passive"))
    )
    (net (code "106") (name "unconnected-(U1D-PD15-Pad62)") (class "Default")
      (node (ref "U1") (pin "62") (pinfunction "PD15_62") (pintype "passive"))
    )
    (net (code "107") (name "unconnected-(U1E-PE0-Pad97)") (class "Default")
      (node (ref "U1") (pin "97") (pinfunction "PE0_97") (pintype "passive"))
    )
    (net (code "108") (name "unconnected-(U1E-PE1-Pad98)") (class "Default")
      (node (ref "U1") (pin "98") (pinfunction "PE1_98") (pintype "passive"))
    )
    (net (code "109") (name "unconnected-(U1E-PE2-Pad1)") (class "Default")
      (node (ref "U1") (pin "1") (pinfunction "PE2_1") (pintype "passive"))
    )
    (net (code "110") (name "unconnected-(U1E-PE3-Pad2)") (class "Default")
      (node (ref "U1") (pin "2") (pinfunction "PE3_2") (pintype "passive"))
    )
    (net (code "111") (name "unconnected-(U1E-PE4-Pad3)") (class "Default")
      (node (ref "U1") (pin "3") (pinfunction "PE4_3") (pintype "passive"))
    )
    (net (code "112") (name "unconnected-(U1E-PE5-Pad4)") (class "Default")
      (node (ref "U1") (pin "4") (pinfunction "PE5_4") (pintype "passive"))
    )
    (net (code "113") (name "unconnected-(U1E-PE6-Pad5)") (class "Default")
      (node (ref "U1") (pin "5") (pinfunction "PE6_5") (pintype "passive"))
    )
    (net (code "114") (name "unconnected-(U1E-PE7-Pad38)") (class "Default")
      (node (ref "U1") (pin "38") (pinfunction "PE7_38") (pintype "passive"))
    )
    (net (code "115") (name "unconnected-(U1E-PE8-Pad39)") (class "Default")
      (node (ref "U1") (pin "39") (pinfunction "PE8_39") (pintype "passive"))
    )
    (net (code "116") (name "unconnected-(U1E-PE9-Pad40)") (class "Default")
      (node (ref "U1") (pin "40") (pinfunction "PE9_40") (pintype "passive"))
    )
    (net (code "117") (name "unconnected-(U1E-PE10-Pad41)") (class "Default")
      (node (ref "U1") (pin "41") (pinfunction "PE10_41") (pintype "passive"))
    )
    (net (code "118") (name "unconnected-(U1E-PE11-Pad42)") (class "Default")
      (node (ref "U1") (pin "42") (pinfunction "PE11_42") (pintype "passive"))
    )
    (net (code "119") (name "unconnected-(U1E-PE12-Pad43)") (class "Default")
      (node (ref "U1") (pin "43") (pinfunction "PE12_43") (pintype "passive"))
    )
    (net (code "120") (name "unconnected-(U1E-PE13-Pad44)") (class "Default")
      (node (ref "U1") (pin "44") (pinfunction "PE13_44") (pintype "passive"))
    )
    (net (code "121") (name "unconnected-(U1E-PE14-Pad45)") (class "Default")
      (node (ref "U1") (pin "45") (pinfunction "PE14_45") (pintype "passive"))
    )
    (net (code "122") (name "unconnected-(U1E-PE15-Pad46)") (class "Default")
      (node (ref "U1") (pin "46") (pinfunction "PE15_46") (pintype "passive"))
    )
  )
)
